# Sensors.net
KiCad netlist of a schematic drawn in EAGLE
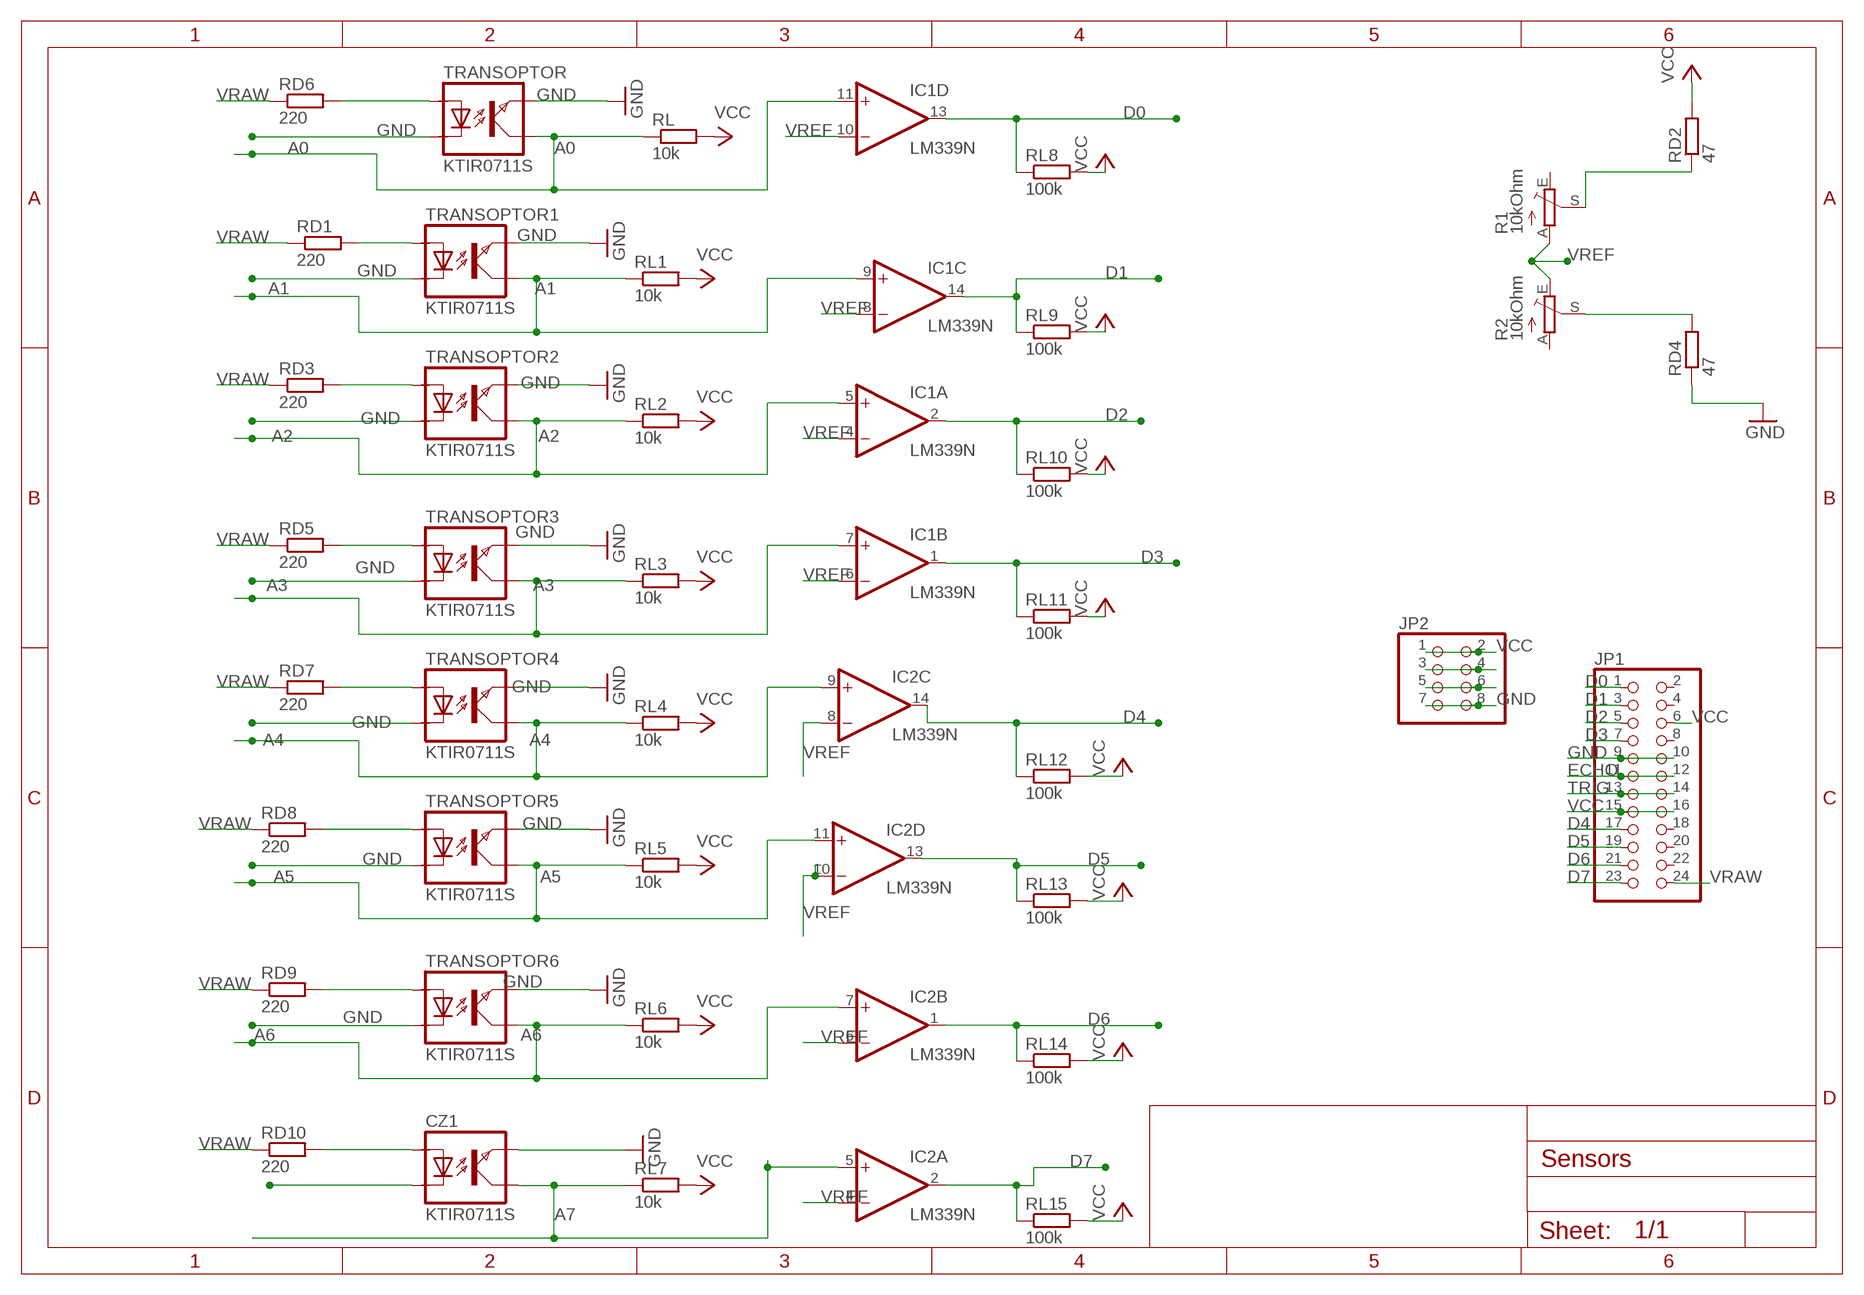
[diagram p0: schematic, sheet 1]

(export (version "E")
  (design (tool "Eeschema 10.0.6"))
  (components
    (comp (ref "CZ1")
      (value "KTIR0711S")
      (footprint "eagle-import:TOP")
      (libsource (lib "eagle-import") (part "KTIR0711S"))
    )
    (comp (ref "IC1")
      (value "LM339N")
      (footprint "eagle-import:DIL14")
      (libsource (lib "eagle-import") (part "LM339N"))
    )
    (comp (ref "IC2")
      (value "LM339N")
      (footprint "eagle-import:DIL14")
      (libsource (lib "eagle-import") (part "LM339N"))
    )
    (comp (ref "JP1")
      (value "PINHD-2X12")
      (footprint "eagle-import:2X12")
      (libsource (lib "eagle-import") (part "PINHD-2X12"))
    )
    (comp (ref "JP2")
      (value "PINHD-2X4")
      (footprint "eagle-import:2X04")
      (libsource (lib "eagle-import") (part "PINHD-2X4"))
    )
    (comp (ref "R1")
      (value "10kOhm")
      (footprint "eagle-import:CA6V")
      (libsource (lib "eagle-import") (part "TRIM_EU-CA6V"))
    )
    (comp (ref "R2")
      (value "10kOhm")
      (footprint "eagle-import:CA6V")
      (libsource (lib "eagle-import") (part "TRIM_EU-CA6V"))
    )
    (comp (ref "RD1")
      (value "220")
      (footprint "eagle-import:0204_7")
      (libsource (lib "eagle-import") (part "R-EU_0204/7"))
    )
    (comp (ref "RD2")
      (value "47")
      (footprint "eagle-import:0204_7")
      (libsource (lib "eagle-import") (part "R-EU_0204/7"))
    )
    (comp (ref "RD3")
      (value "220")
      (footprint "eagle-import:0204_7")
      (libsource (lib "eagle-import") (part "R-EU_0204/7"))
    )
    (comp (ref "RD4")
      (value "47")
      (footprint "eagle-import:0204_7")
      (libsource (lib "eagle-import") (part "R-EU_0204/7"))
    )
    (comp (ref "RD5")
      (value "220")
      (footprint "eagle-import:0204_7")
      (libsource (lib "eagle-import") (part "R-EU_0204/7"))
    )
    (comp (ref "RD6")
      (value "220")
      (footprint "eagle-import:0204_7")
      (libsource (lib "eagle-import") (part "R-EU_0204/7"))
    )
    (comp (ref "RD7")
      (value "220")
      (footprint "eagle-import:0204_7")
      (libsource (lib "eagle-import") (part "R-EU_0204/7"))
    )
    (comp (ref "RD8")
      (value "220")
      (footprint "eagle-import:0204_7")
      (libsource (lib "eagle-import") (part "R-EU_0204/7"))
    )
    (comp (ref "RD9")
      (value "220")
      (footprint "eagle-import:0204_7")
      (libsource (lib "eagle-import") (part "R-EU_0204/7"))
    )
    (comp (ref "RD10")
      (value "220")
      (footprint "eagle-import:0204_7")
      (libsource (lib "eagle-import") (part "R-EU_0204/7"))
    )
    (comp (ref "RL")
      (value "10k")
      (footprint "eagle-import:0204_7")
      (libsource (lib "eagle-import") (part "R-EU_0204/7"))
    )
    (comp (ref "RL1")
      (value "10k")
      (footprint "eagle-import:0204_7")
      (libsource (lib "eagle-import") (part "R-EU_0204/7"))
    )
    (comp (ref "RL2")
      (value "10k")
      (footprint "eagle-import:0204_7")
      (libsource (lib "eagle-import") (part "R-EU_0204/7"))
    )
    (comp (ref "RL3")
      (value "10k")
      (footprint "eagle-import:0204_7")
      (libsource (lib "eagle-import") (part "R-EU_0204/7"))
    )
    (comp (ref "RL4")
      (value "10k")
      (footprint "eagle-import:0204_7")
      (libsource (lib "eagle-import") (part "R-EU_0204/7"))
    )
    (comp (ref "RL5")
      (value "10k")
      (footprint "eagle-import:0204_7")
      (libsource (lib "eagle-import") (part "R-EU_0204/7"))
    )
    (comp (ref "RL6")
      (value "10k")
      (footprint "eagle-import:0204_7")
      (libsource (lib "eagle-import") (part "R-EU_0204/7"))
    )
    (comp (ref "RL7")
      (value "10k")
      (footprint "eagle-import:0204_7")
      (libsource (lib "eagle-import") (part "R-EU_0204/7"))
    )
    (comp (ref "RL8")
      (value "100k")
      (footprint "eagle-import:0204_7")
      (libsource (lib "eagle-import") (part "R-EU_0204/7"))
    )
    (comp (ref "RL9")
      (value "100k")
      (footprint "eagle-import:0204_7")
      (libsource (lib "eagle-import") (part "R-EU_0204/7"))
    )
    (comp (ref "RL10")
      (value "100k")
      (footprint "eagle-import:0204_7")
      (libsource (lib "eagle-import") (part "R-EU_0204/7"))
    )
    (comp (ref "RL11")
      (value "100k")
      (footprint "eagle-import:0204_7")
      (libsource (lib "eagle-import") (part "R-EU_0204/7"))
    )
    (comp (ref "RL12")
      (value "100k")
      (footprint "eagle-import:0204_7")
      (libsource (lib "eagle-import") (part "R-EU_0204/7"))
    )
    (comp (ref "RL13")
      (value "100k")
      (footprint "eagle-import:0204_7")
      (libsource (lib "eagle-import") (part "R-EU_0204/7"))
    )
    (comp (ref "RL14")
      (value "100k")
      (footprint "eagle-import:0204_7")
      (libsource (lib "eagle-import") (part "R-EU_0204/7"))
    )
    (comp (ref "RL15")
      (value "100k")
      (footprint "eagle-import:0204_7")
      (libsource (lib "eagle-import") (part "R-EU_0204/7"))
    )
    (comp (ref "TRANSOPTOR")
      (value "KTIR0711S")
      (footprint "eagle-import:TOP")
      (libsource (lib "eagle-import") (part "KTIR0711S"))
    )
    (comp (ref "TRANSOPTOR1")
      (value "KTIR0711S")
      (footprint "eagle-import:TOP")
      (libsource (lib "eagle-import") (part "KTIR0711S"))
    )
    (comp (ref "TRANSOPTOR2")
      (value "KTIR0711S")
      (footprint "eagle-import:TOP")
      (libsource (lib "eagle-import") (part "KTIR0711S"))
    )
    (comp (ref "TRANSOPTOR3")
      (value "KTIR0711S")
      (footprint "eagle-import:TOP")
      (libsource (lib "eagle-import") (part "KTIR0711S"))
    )
    (comp (ref "TRANSOPTOR4")
      (value "KTIR0711S")
      (footprint "eagle-import:TOP")
      (libsource (lib "eagle-import") (part "KTIR0711S"))
    )
    (comp (ref "TRANSOPTOR5")
      (value "KTIR0711S")
      (footprint "eagle-import:TOP")
      (libsource (lib "eagle-import") (part "KTIR0711S"))
    )
    (comp (ref "TRANSOPTOR6")
      (value "KTIR0711S")
      (footprint "eagle-import:TOP")
      (libsource (lib "eagle-import") (part "KTIR0711S"))
    )
  )
  (nets
    (net (code "1") (name "/A0") (class "Default")
      (node (ref "IC1") (pin "11") (pinfunction "+IN_11") (pintype "input"))
      (node (ref "RL") (pin "1") (pinfunction "1_1") (pintype "passive"))
      (node (ref "TRANSOPTOR") (pin "KOLEKTOR") (pinfunction "KOLEKTOR_KOLEKTOR") (pintype "bidirectional"))
    )
    (net (code "2") (name "/A1") (class "Default")
      (node (ref "IC1") (pin "9") (pinfunction "+IN_9") (pintype "input"))
      (node (ref "RL1") (pin "1") (pinfunction "1_1") (pintype "passive"))
      (node (ref "TRANSOPTOR1") (pin "KOLEKTOR") (pinfunction "KOLEKTOR_KOLEKTOR") (pintype "bidirectional"))
    )
    (net (code "3") (name "/A2") (class "Default")
      (node (ref "IC1") (pin "5") (pinfunction "+IN_5") (pintype "input"))
      (node (ref "RL2") (pin "1") (pinfunction "1_1") (pintype "passive"))
      (node (ref "TRANSOPTOR2") (pin "KOLEKTOR") (pinfunction "KOLEKTOR_KOLEKTOR") (pintype "bidirectional"))
    )
    (net (code "4") (name "/A3") (class "Default")
      (node (ref "IC1") (pin "7") (pinfunction "+IN_7") (pintype "input"))
      (node (ref "RL3") (pin "1") (pinfunction "1_1") (pintype "passive"))
      (node (ref "TRANSOPTOR3") (pin "KOLEKTOR") (pinfunction "KOLEKTOR_KOLEKTOR") (pintype "bidirectional"))
    )
    (net (code "5") (name "/A4") (class "Default")
      (node (ref "IC2") (pin "9") (pinfunction "+IN_9") (pintype "input"))
      (node (ref "RL4") (pin "1") (pinfunction "1_1") (pintype "passive"))
      (node (ref "TRANSOPTOR4") (pin "KOLEKTOR") (pinfunction "KOLEKTOR_KOLEKTOR") (pintype "bidirectional"))
    )
    (net (code "6") (name "/A5") (class "Default")
      (node (ref "IC2") (pin "11") (pinfunction "+IN_11") (pintype "input"))
      (node (ref "RL5") (pin "1") (pinfunction "1_1") (pintype "passive"))
      (node (ref "TRANSOPTOR5") (pin "KOLEKTOR") (pinfunction "KOLEKTOR_KOLEKTOR") (pintype "bidirectional"))
    )
    (net (code "7") (name "/A6") (class "Default")
      (node (ref "IC2") (pin "7") (pinfunction "+IN_7") (pintype "input"))
      (node (ref "RL6") (pin "1") (pinfunction "1_1") (pintype "passive"))
      (node (ref "TRANSOPTOR6") (pin "KOLEKTOR") (pinfunction "KOLEKTOR_KOLEKTOR") (pintype "bidirectional"))
    )
    (net (code "8") (name "/A7") (class "Default")
      (node (ref "CZ1") (pin "KOLEKTOR") (pinfunction "KOLEKTOR_KOLEKTOR") (pintype "bidirectional"))
      (node (ref "IC2") (pin "5") (pinfunction "+IN_5") (pintype "input"))
      (node (ref "RL7") (pin "1") (pinfunction "1_1") (pintype "passive"))
    )
    (net (code "9") (name "/D0") (class "Default")
      (node (ref "IC1") (pin "13") (pinfunction "OUT_13") (pintype "open_collector"))
      (node (ref "JP1") (pin "1") (pinfunction "1_1") (pintype "passive"))
      (node (ref "RL8") (pin "1") (pinfunction "1_1") (pintype "passive"))
    )
    (net (code "10") (name "/D1") (class "Default")
      (node (ref "IC1") (pin "14") (pinfunction "OUT_14") (pintype "open_collector"))
      (node (ref "JP1") (pin "3") (pinfunction "3_3") (pintype "passive"))
      (node (ref "RL9") (pin "1") (pinfunction "1_1") (pintype "passive"))
    )
    (net (code "11") (name "/D2") (class "Default")
      (node (ref "IC1") (pin "2") (pinfunction "OUT_2") (pintype "open_collector"))
      (node (ref "JP1") (pin "5") (pinfunction "5_5") (pintype "passive"))
      (node (ref "RL10") (pin "1") (pinfunction "1_1") (pintype "passive"))
    )
    (net (code "12") (name "/D3") (class "Default")
      (node (ref "IC1") (pin "1") (pinfunction "OUT_1") (pintype "open_collector"))
      (node (ref "JP1") (pin "7") (pinfunction "7_7") (pintype "passive"))
      (node (ref "RL11") (pin "1") (pinfunction "1_1") (pintype "passive"))
    )
    (net (code "13") (name "/D4") (class "Default")
      (node (ref "IC2") (pin "14") (pinfunction "OUT_14") (pintype "open_collector"))
      (node (ref "JP1") (pin "17") (pinfunction "17_17") (pintype "passive"))
      (node (ref "RL12") (pin "1") (pinfunction "1_1") (pintype "passive"))
    )
    (net (code "14") (name "/D5") (class "Default")
      (node (ref "IC2") (pin "13") (pinfunction "OUT_13") (pintype "open_collector"))
      (node (ref "JP1") (pin "19") (pinfunction "19_19") (pintype "passive"))
      (node (ref "RL13") (pin "1") (pinfunction "1_1") (pintype "passive"))
    )
    (net (code "15") (name "/D6") (class "Default")
      (node (ref "IC2") (pin "1") (pinfunction "OUT_1") (pintype "open_collector"))
      (node (ref "JP1") (pin "21") (pinfunction "21_21") (pintype "passive"))
      (node (ref "RL14") (pin "1") (pinfunction "1_1") (pintype "passive"))
    )
    (net (code "16") (name "/D7") (class "Default")
      (node (ref "IC2") (pin "2") (pinfunction "OUT_2") (pintype "open_collector"))
      (node (ref "JP1") (pin "23") (pinfunction "23_23") (pintype "passive"))
      (node (ref "RL15") (pin "1") (pinfunction "1_1") (pintype "passive"))
    )
    (net (code "17") (name "/ECHO") (class "Default")
      (node (ref "JP1") (pin "11") (pinfunction "11_11") (pintype "passive"))
      (node (ref "JP1") (pin "12") (pinfunction "12_12") (pintype "passive"))
      (node (ref "JP2") (pin "5") (pinfunction "5_5") (pintype "passive"))
      (node (ref "JP2") (pin "6") (pinfunction "6_6") (pintype "passive"))
    )
    (net (code "18") (name "/TRIG") (class "Default")
      (node (ref "JP1") (pin "13") (pinfunction "13_13") (pintype "passive"))
      (node (ref "JP1") (pin "14") (pinfunction "14_14") (pintype "passive"))
      (node (ref "JP2") (pin "3") (pinfunction "3_3") (pintype "passive"))
      (node (ref "JP2") (pin "4") (pinfunction "4_4") (pintype "passive"))
    )
    (net (code "19") (name "/VRAW") (class "Default")
      (node (ref "JP1") (pin "24") (pinfunction "24_24") (pintype "passive"))
      (node (ref "RD1") (pin "1") (pinfunction "1_1") (pintype "passive"))
      (node (ref "RD10") (pin "1") (pinfunction "1_1") (pintype "passive"))
      (node (ref "RD3") (pin "1") (pinfunction "1_1") (pintype "passive"))
      (node (ref "RD5") (pin "1") (pinfunction "1_1") (pintype "passive"))
      (node (ref "RD6") (pin "1") (pinfunction "1_1") (pintype "passive"))
      (node (ref "RD7") (pin "1") (pinfunction "1_1") (pintype "passive"))
      (node (ref "RD8") (pin "1") (pinfunction "1_1") (pintype "passive"))
      (node (ref "RD9") (pin "1") (pinfunction "1_1") (pintype "passive"))
    )
    (net (code "20") (name "/VREF") (class "Default")
      (node (ref "IC1") (pin "10") (pinfunction "-IN_10") (pintype "input"))
      (node (ref "IC1") (pin "4") (pinfunction "-IN_4") (pintype "input"))
      (node (ref "IC1") (pin "6") (pinfunction "-IN_6") (pintype "input"))
      (node (ref "IC1") (pin "8") (pinfunction "-IN_8") (pintype "input"))
      (node (ref "IC2") (pin "10") (pinfunction "-IN_10") (pintype "input"))
      (node (ref "IC2") (pin "4") (pinfunction "-IN_4") (pintype "input"))
      (node (ref "IC2") (pin "6") (pinfunction "-IN_6") (pintype "input"))
      (node (ref "IC2") (pin "8") (pinfunction "-IN_8") (pintype "input"))
      (node (ref "R1") (pin "A") (pinfunction "A_A") (pintype "passive"))
      (node (ref "R2") (pin "E") (pinfunction "E_E") (pintype "passive"))
    )
    (net (code "21") (name "GND") (class "Default")
      (node (ref "CZ1") (pin "EMITER") (pinfunction "EMITER_EMITER") (pintype "bidirectional"))
      (node (ref "CZ1") (pin "KATODA") (pinfunction "KATODA_KATODA") (pintype "passive"))
      (node (ref "JP1") (pin "10") (pinfunction "10_10") (pintype "passive"))
      (node (ref "JP1") (pin "9") (pinfunction "9_9") (pintype "passive"))
      (node (ref "JP2") (pin "7") (pinfunction "7_7") (pintype "passive"))
      (node (ref "JP2") (pin "8") (pinfunction "8_8") (pintype "passive"))
      (node (ref "RD4") (pin "1") (pinfunction "1_1") (pintype "passive"))
      (node (ref "TRANSOPTOR") (pin "EMITER") (pinfunction "EMITER_EMITER") (pintype "bidirectional"))
      (node (ref "TRANSOPTOR") (pin "KATODA") (pinfunction "KATODA_KATODA") (pintype "passive"))
      (node (ref "TRANSOPTOR1") (pin "EMITER") (pinfunction "EMITER_EMITER") (pintype "bidirectional"))
      (node (ref "TRANSOPTOR1") (pin "KATODA") (pinfunction "KATODA_KATODA") (pintype "passive"))
      (node (ref "TRANSOPTOR2") (pin "EMITER") (pinfunction "EMITER_EMITER") (pintype "bidirectional"))
      (node (ref "TRANSOPTOR2") (pin "KATODA") (pinfunction "KATODA_KATODA") (pintype "passive"))
      (node (ref "TRANSOPTOR3") (pin "EMITER") (pinfunction "EMITER_EMITER") (pintype "bidirectional"))
      (node (ref "TRANSOPTOR3") (pin "KATODA") (pinfunction "KATODA_KATODA") (pintype "passive"))
      (node (ref "TRANSOPTOR4") (pin "EMITER") (pinfunction "EMITER_EMITER") (pintype "bidirectional"))
      (node (ref "TRANSOPTOR4") (pin "KATODA") (pinfunction "KATODA_KATODA") (pintype "passive"))
      (node (ref "TRANSOPTOR5") (pin "EMITER") (pinfunction "EMITER_EMITER") (pintype "bidirectional"))
      (node (ref "TRANSOPTOR5") (pin "KATODA") (pinfunction "KATODA_KATODA") (pintype "passive"))
      (node (ref "TRANSOPTOR6") (pin "EMITER") (pinfunction "EMITER_EMITER") (pintype "bidirectional"))
      (node (ref "TRANSOPTOR6") (pin "KATODA") (pinfunction "KATODA_KATODA") (pintype "passive"))
    )
    (net (code "22") (name "Net-(CZ1-PadANODA)") (class "Default")
      (node (ref "CZ1") (pin "ANODA") (pinfunction "ANODA_ANODA") (pintype "passive"))
      (node (ref "RD10") (pin "2") (pinfunction "2_2") (pintype "passive"))
    )
    (net (code "23") (name "Net-(R1-PadS)") (class "Default")
      (node (ref "R1") (pin "S") (pinfunction "S_S") (pintype "passive"))
      (node (ref "RD2") (pin "1") (pinfunction "1_1") (pintype "passive"))
    )
    (net (code "24") (name "Net-(R2-PadS)") (class "Default")
      (node (ref "R2") (pin "S") (pinfunction "S_S") (pintype "passive"))
      (node (ref "RD4") (pin "2") (pinfunction "2_2") (pintype "passive"))
    )
    (net (code "25") (name "Net-(RD1-Pad2)") (class "Default")
      (node (ref "RD1") (pin "2") (pinfunction "2_2") (pintype "passive"))
      (node (ref "TRANSOPTOR1") (pin "ANODA") (pinfunction "ANODA_ANODA") (pintype "passive"))
    )
    (net (code "26") (name "Net-(RD3-Pad2)") (class "Default")
      (node (ref "RD3") (pin "2") (pinfunction "2_2") (pintype "passive"))
      (node (ref "TRANSOPTOR2") (pin "ANODA") (pinfunction "ANODA_ANODA") (pintype "passive"))
    )
    (net (code "27") (name "Net-(RD5-Pad2)") (class "Default")
      (node (ref "RD5") (pin "2") (pinfunction "2_2") (pintype "passive"))
      (node (ref "TRANSOPTOR3") (pin "ANODA") (pinfunction "ANODA_ANODA") (pintype "passive"))
    )
    (net (code "28") (name "Net-(RD6-Pad2)") (class "Default")
      (node (ref "RD6") (pin "2") (pinfunction "2_2") (pintype "passive"))
      (node (ref "TRANSOPTOR") (pin "ANODA") (pinfunction "ANODA_ANODA") (pintype "passive"))
    )
    (net (code "29") (name "Net-(RD7-Pad2)") (class "Default")
      (node (ref "RD7") (pin "2") (pinfunction "2_2") (pintype "passive"))
      (node (ref "TRANSOPTOR4") (pin "ANODA") (pinfunction "ANODA_ANODA") (pintype "passive"))
    )
    (net (code "30") (name "Net-(RD8-Pad2)") (class "Default")
      (node (ref "RD8") (pin "2") (pinfunction "2_2") (pintype "passive"))
      (node (ref "TRANSOPTOR5") (pin "ANODA") (pinfunction "ANODA_ANODA") (pintype "passive"))
    )
    (net (code "31") (name "Net-(RD9-Pad2)") (class "Default")
      (node (ref "RD9") (pin "2") (pinfunction "2_2") (pintype "passive"))
      (node (ref "TRANSOPTOR6") (pin "ANODA") (pinfunction "ANODA_ANODA") (pintype "passive"))
    )
    (net (code "32") (name "VCC") (class "Default")
      (node (ref "JP1") (pin "15") (pinfunction "15_15") (pintype "passive"))
      (node (ref "JP1") (pin "16") (pinfunction "16_16") (pintype "passive"))
      (node (ref "JP1") (pin "6") (pinfunction "6_6") (pintype "passive"))
      (node (ref "JP2") (pin "1") (pinfunction "1_1") (pintype "passive"))
      (node (ref "JP2") (pin "2") (pinfunction "2_2") (pintype "passive"))
      (node (ref "RD2") (pin "2") (pinfunction "2_2") (pintype "passive"))
      (node (ref "RL") (pin "2") (pinfunction "2_2") (pintype "passive"))
      (node (ref "RL1") (pin "2") (pinfunction "2_2") (pintype "passive"))
      (node (ref "RL10") (pin "2") (pinfunction "2_2") (pintype "passive"))
      (node (ref "RL11") (pin "2") (pinfunction "2_2") (pintype "passive"))
      (node (ref "RL12") (pin "2") (pinfunction "2_2") (pintype "passive"))
      (node (ref "RL13") (pin "2") (pinfunction "2_2") (pintype "passive"))
      (node (ref "RL14") (pin "2") (pinfunction "2_2") (pintype "passive"))
      (node (ref "RL15") (pin "2") (pinfunction "2_2") (pintype "passive"))
      (node (ref "RL2") (pin "2") (pinfunction "2_2") (pintype "passive"))
      (node (ref "RL3") (pin "2") (pinfunction "2_2") (pintype "passive"))
      (node (ref "RL4") (pin "2") (pinfunction "2_2") (pintype "passive"))
      (node (ref "RL5") (pin "2") (pinfunction "2_2") (pintype "passive"))
      (node (ref "RL6") (pin "2") (pinfunction "2_2") (pintype "passive"))
      (node (ref "RL7") (pin "2") (pinfunction "2_2") (pintype "passive"))
      (node (ref "RL8") (pin "2") (pinfunction "2_2") (pintype "passive"))
      (node (ref "RL9") (pin "2") (pinfunction "2_2") (pintype "passive"))
    )
    (net (code "33") (name "unconnected-(JP1-Pad2)") (class "Default")
      (node (ref "JP1") (pin "2") (pinfunction "2_2") (pintype "passive"))
    )
    (net (code "34") (name "unconnected-(JP1-Pad4)") (class "Default")
      (node (ref "JP1") (pin "4") (pinfunction "4_4") (pintype "passive"))
    )
    (net (code "35") (name "unconnected-(JP1-Pad8)") (class "Default")
      (node (ref "JP1") (pin "8") (pinfunction "8_8") (pintype "passive"))
    )
    (net (code "36") (name "unconnected-(JP1-Pad18)") (class "Default")
      (node (ref "JP1") (pin "18") (pinfunction "18_18") (pintype "passive"))
    )
    (net (code "37") (name "unconnected-(JP1-Pad20)") (class "Default")
      (node (ref "JP1") (pin "20") (pinfunction "20_20") (pintype "passive"))
    )
    (net (code "38") (name "unconnected-(JP1-Pad22)") (class "Default")
      (node (ref "JP1") (pin "22") (pinfunction "22_22") (pintype "passive"))
    )
    (net (code "39") (name "unconnected-(R1-PadE)") (class "Default")
      (node (ref "R1") (pin "E") (pinfunction "E_E") (pintype "passive"))
    )
    (net (code "40") (name "unconnected-(R2-PadA)") (class "Default")
      (node (ref "R2") (pin "A") (pinfunction "A_A") (pintype "passive"))
    )
  )
)
